# untitled.net
KiCad netlist of a schematic drawn in EAGLE
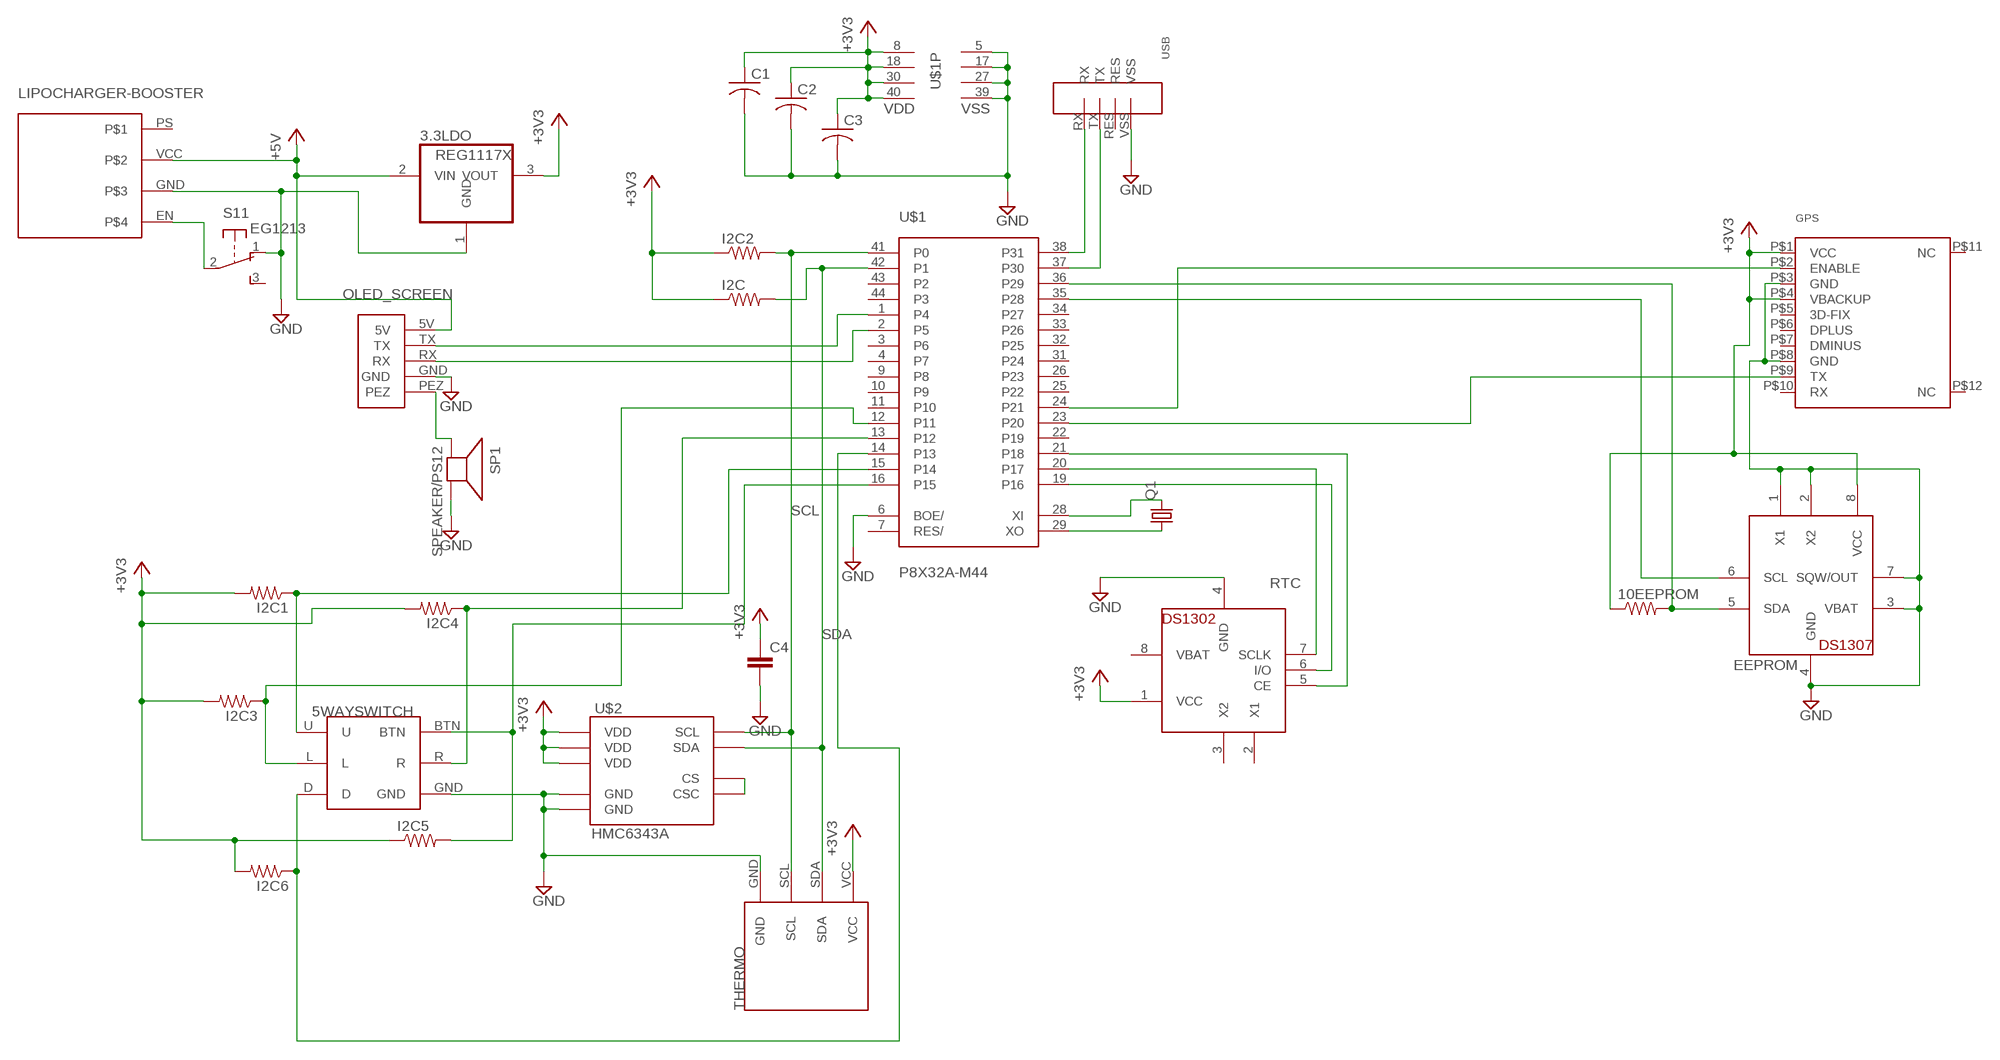
[diagram p0: schematic, sheet 1]

(export (version "E")
  (design (tool "Eeschema 10.0.6"))
  (components
    (comp (ref "3.3LDO")
      (value "REG1117X")
      (footprint "eagle-import:TO252")
      (libsource (lib "eagle-import") (part "REG1117X"))
    )
    (comp (ref "5WAYSWITCH")
      (value "5-WAYSWITCH")
      (footprint "eagle-import:5-WAYSWITCH")
      (libsource (lib "eagle-import") (part "5-WAYSWITCH"))
    )
    (comp (ref "10EEPROM")
      (value "R-US_R1005")
      (footprint "eagle-import:R1005")
      (libsource (lib "eagle-import") (part "R-US_R1005"))
    )
    (comp (ref "C1")
      (value "C-USC0603")
      (footprint "eagle-import:C0603")
      (libsource (lib "eagle-import") (part "C-USC0603"))
    )
    (comp (ref "C2")
      (value "C-USC0603")
      (footprint "eagle-import:C0603")
      (libsource (lib "eagle-import") (part "C-USC0603"))
    )
    (comp (ref "C3")
      (value "C-USC0603")
      (footprint "eagle-import:C0603")
      (libsource (lib "eagle-import") (part "C-USC0603"))
    )
    (comp (ref "C4")
      (value "CAP0603")
      (footprint "eagle-import:0603")
      (libsource (lib "eagle-import") (part "CAP0603"))
    )
    (comp (ref "EEPROM")
      (value "DS1307")
      (footprint "eagle-import:DIL08")
      (libsource (lib "eagle-import") (part "DS1307"))
    )
    (comp (ref "GPS")
      (value "GPS_FGPMMOPA6B")
      (footprint "eagle-import:FGPMMOPA6B")
      (libsource (lib "eagle-import") (part "GPS_FGPMMOPA6B"))
    )
    (comp (ref "I2C")
      (value "R-US_R1005")
      (footprint "eagle-import:R1005")
      (libsource (lib "eagle-import") (part "R-US_R1005"))
    )
    (comp (ref "I2C1")
      (value "R-US_R1005")
      (footprint "eagle-import:R1005")
      (libsource (lib "eagle-import") (part "R-US_R1005"))
    )
    (comp (ref "I2C2")
      (value "R-US_R1005")
      (footprint "eagle-import:R1005")
      (libsource (lib "eagle-import") (part "R-US_R1005"))
    )
    (comp (ref "I2C3")
      (value "R-US_R1005")
      (footprint "eagle-import:R1005")
      (libsource (lib "eagle-import") (part "R-US_R1005"))
    )
    (comp (ref "I2C4")
      (value "R-US_R1005")
      (footprint "eagle-import:R1005")
      (libsource (lib "eagle-import") (part "R-US_R1005"))
    )
    (comp (ref "I2C5")
      (value "R-US_R1005")
      (footprint "eagle-import:R1005")
      (libsource (lib "eagle-import") (part "R-US_R1005"))
    )
    (comp (ref "I2C6")
      (value "R-US_R1005")
      (footprint "eagle-import:R1005")
      (libsource (lib "eagle-import") (part "R-US_R1005"))
    )
    (comp (ref "LIPOCHARGER-BOOSTER")
      (value "SFLIPO")
      (footprint "eagle-import:SFLIPO")
      (libsource (lib "eagle-import") (part "SFLIPO"))
    )
    (comp (ref "OLED_SCREEN")
      (value "4DSCREEN")
      (footprint "eagle-import:4DSCREEN")
      (libsource (lib "eagle-import") (part "4DSCREEN"))
    )
    (comp (ref "Q1")
      (value "CRYSTALHC49S")
      (footprint "eagle-import:HC49_S")
      (libsource (lib "eagle-import") (part "CRYSTALHC49S"))
    )
    (comp (ref "RTC")
      (value "DS1302")
      (footprint "eagle-import:DIL08-ROUND")
      (libsource (lib "eagle-import") (part "DS1302"))
    )
    (comp (ref "S1")
      (value "EG1213")
      (footprint "eagle-import:EG1213")
      (libsource (lib "eagle-import") (part "EG1213"))
    )
    (comp (ref "SP1")
      (value "SPEAKER/PS12")
      (footprint "eagle-import:PS12")
      (libsource (lib "eagle-import") (part "SPEAKER/PS12"))
    )
    (comp (ref "THERMO")
      (value "SFTEMP")
      (footprint "eagle-import:SFTEMP")
      (libsource (lib "eagle-import") (part "SFTEMP"))
    )
    (comp (ref "U$1")
      (value "P8X32A-M44")
      (footprint "eagle-import:P8X32A-M44")
      (libsource (lib "eagle-import") (part "P8X32A-M44"))
    )
    (comp (ref "U$2")
      (value "HMC6343A")
      (footprint "eagle-import:LCC36")
      (libsource (lib "eagle-import") (part "HMC6343A"))
    )
    (comp (ref "USB")
      (value "4PINUSB")
      (footprint "eagle-import:4PINUSB")
      (libsource (lib "eagle-import") (part "4PINUSB"))
    )
  )
  (nets
    (net (code "1") (name "+3V3") (class "Default")
      (node (ref "10EEPROM") (pin "1") (pinfunction "1_1") (pintype "passive"))
      (node (ref "3.3LDO") (pin "3") (pinfunction "VOUT_3") (pintype "output"))
      (node (ref "C1") (pin "1") (pinfunction "1_1") (pintype "passive"))
      (node (ref "C2") (pin "1") (pinfunction "1_1") (pintype "passive"))
      (node (ref "C3") (pin "1") (pinfunction "1_1") (pintype "passive"))
      (node (ref "C4") (pin "1") (pinfunction "1_1") (pintype "passive"))
      (node (ref "EEPROM") (pin "8") (pinfunction "VCC_8") (pintype "power_in"))
      (node (ref "GPS") (pin "P$1") (pinfunction "VCC_P$1") (pintype "bidirectional"))
      (node (ref "GPS") (pin "P$4") (pinfunction "VBACKUP_P$4") (pintype "bidirectional"))
      (node (ref "I2C") (pin "1") (pinfunction "1_1") (pintype "passive"))
      (node (ref "I2C1") (pin "2") (pinfunction "2_2") (pintype "passive"))
      (node (ref "I2C2") (pin "1") (pinfunction "1_1") (pintype "passive"))
      (node (ref "I2C3") (pin "2") (pinfunction "2_2") (pintype "passive"))
      (node (ref "I2C4") (pin "2") (pinfunction "2_2") (pintype "passive"))
      (node (ref "I2C5") (pin "1") (pinfunction "1_1") (pintype "passive"))
      (node (ref "I2C6") (pin "2") (pinfunction "2_2") (pintype "passive"))
      (node (ref "RTC") (pin "1") (pinfunction "VCC_1") (pintype "power_in"))
      (node (ref "THERMO") (pin "VCC") (pinfunction "VCC_VCC") (pintype "bidirectional"))
      (node (ref "U$1") (pin "18") (pinfunction "VDD_18") (pintype "power_in"))
      (node (ref "U$1") (pin "30") (pinfunction "VDD_30") (pintype "power_in"))
      (node (ref "U$1") (pin "40") (pinfunction "VDD_40") (pintype "power_in"))
      (node (ref "U$1") (pin "8") (pinfunction "VDD_8") (pintype "power_in"))
      (node (ref "U$2") (pin "11") (pinfunction "VDD_11") (pintype "bidirectional"))
      (node (ref "U$2") (pin "21") (pinfunction "VDD_21") (pintype "bidirectional"))
      (node (ref "U$2") (pin "3") (pinfunction "VDD_3") (pintype "bidirectional"))
    )
    (net (code "2") (name "+5V") (class "Default")
      (node (ref "3.3LDO") (pin "2") (pinfunction "VIN_2") (pintype "input"))
      (node (ref "LIPOCHARGER-BOOSTER") (pin "VCC") (pinfunction "P$2_VCC") (pintype "bidirectional"))
      (node (ref "OLED_SCREEN") (pin "5V") (pinfunction "5V_5V") (pintype "bidirectional"))
    )
    (net (code "3") (name "/SCL") (class "Default")
      (node (ref "I2C2") (pin "2") (pinfunction "2_2") (pintype "passive"))
      (node (ref "THERMO") (pin "SCL") (pinfunction "SCL_SCL") (pintype "bidirectional"))
      (node (ref "U$1") (pin "41") (pinfunction "P0_41") (pintype "bidirectional"))
      (node (ref "U$2") (pin "32") (pinfunction "SCL_32") (pintype "bidirectional"))
    )
    (net (code "4") (name "/SDA") (class "Default")
      (node (ref "I2C") (pin "2") (pinfunction "2_2") (pintype "passive"))
      (node (ref "THERMO") (pin "SDA") (pinfunction "SDA_SDA") (pintype "bidirectional"))
      (node (ref "U$1") (pin "42") (pinfunction "P1_42") (pintype "bidirectional"))
      (node (ref "U$2") (pin "36") (pinfunction "SDA_36") (pintype "bidirectional"))
    )
    (net (code "5") (name "/VBAT") (class "Default")
      (node (ref "RTC") (pin "8") (pinfunction "VBAT_8") (pintype "power_in"))
    )
    (net (code "6") (name "GND") (class "Default")
      (node (ref "3.3LDO") (pin "1") (pinfunction "GND_1") (pintype "power_in"))
      (node (ref "5WAYSWITCH") (pin "GND") (pinfunction "GND_GND") (pintype "bidirectional"))
      (node (ref "C1") (pin "2") (pinfunction "2_2") (pintype "passive"))
      (node (ref "C2") (pin "2") (pinfunction "2_2") (pintype "passive"))
      (node (ref "C3") (pin "2") (pinfunction "2_2") (pintype "passive"))
      (node (ref "C4") (pin "2") (pinfunction "2_2") (pintype "passive"))
      (node (ref "EEPROM") (pin "1") (pinfunction "X1_1") (pintype "passive"))
      (node (ref "EEPROM") (pin "2") (pinfunction "X2_2") (pintype "passive"))
      (node (ref "EEPROM") (pin "3") (pinfunction "VBAT_3") (pintype "power_in"))
      (node (ref "EEPROM") (pin "4") (pinfunction "GND_4") (pintype "power_in"))
      (node (ref "EEPROM") (pin "7") (pinfunction "SQW/OUT_7") (pintype "bidirectional"))
      (node (ref "GPS") (pin "P$3") (pinfunction "GND_P$3") (pintype "bidirectional"))
      (node (ref "GPS") (pin "P$8") (pinfunction "GND_P$8") (pintype "bidirectional"))
      (node (ref "LIPOCHARGER-BOOSTER") (pin "GND") (pinfunction "P$3_GND") (pintype "bidirectional"))
      (node (ref "OLED_SCREEN") (pin "GND") (pinfunction "GND_GND") (pintype "bidirectional"))
      (node (ref "RTC") (pin "4") (pinfunction "GND_4") (pintype "power_in"))
      (node (ref "S1") (pin "1") (pinfunction "O_1") (pintype "passive"))
      (node (ref "SP1") (pin "P$2") (pinfunction "-_P$2") (pintype "passive"))
      (node (ref "THERMO") (pin "GND") (pinfunction "GND_GND") (pintype "bidirectional"))
      (node (ref "U$1") (pin "17") (pinfunction "VSS_17") (pintype "power_in"))
      (node (ref "U$1") (pin "27") (pinfunction "VSS_27") (pintype "power_in"))
      (node (ref "U$1") (pin "39") (pinfunction "VSS_39") (pintype "power_in"))
      (node (ref "U$1") (pin "5") (pinfunction "VSS_5") (pintype "power_in"))
      (node (ref "U$1") (pin "6") (pinfunction "BOE/_6") (pintype "input"))
      (node (ref "U$2") (pin "25") (pinfunction "GND_25") (pintype "bidirectional"))
      (node (ref "U$2") (pin "29") (pinfunction "GND_29") (pintype "bidirectional"))
      (node (ref "USB") (pin "VSS") (pinfunction "VSS_VSS") (pintype "bidirectional"))
    )
    (net (code "7") (name "Net-(EEPROM-SCL)") (class "Default")
      (node (ref "EEPROM") (pin "6") (pinfunction "SCL_6") (pintype "bidirectional"))
      (node (ref "U$1") (pin "35") (pinfunction "P28_35") (pintype "bidirectional"))
    )
    (net (code "8") (name "Net-(EEPROM-SDA)") (class "Default")
      (node (ref "10EEPROM") (pin "2") (pinfunction "2_2") (pintype "passive"))
      (node (ref "EEPROM") (pin "5") (pinfunction "SDA_5") (pintype "bidirectional"))
      (node (ref "U$1") (pin "36") (pinfunction "P29_36") (pintype "bidirectional"))
    )
    (net (code "9") (name "Net-(GPS-ENABLE)") (class "Default")
      (node (ref "GPS") (pin "P$2") (pinfunction "ENABLE_P$2") (pintype "bidirectional"))
      (node (ref "U$1") (pin "24") (pinfunction "P21_24") (pintype "bidirectional"))
    )
    (net (code "10") (name "Net-(GPS-TX)") (class "Default")
      (node (ref "GPS") (pin "P$9") (pinfunction "TX_P$9") (pintype "bidirectional"))
      (node (ref "U$1") (pin "23") (pinfunction "P20_23") (pintype "bidirectional"))
    )
    (net (code "11") (name "Net-(LIPOCHARGER-BOOSTER-P$4)") (class "Default")
      (node (ref "LIPOCHARGER-BOOSTER") (pin "EN") (pinfunction "P$4_EN") (pintype "bidirectional"))
      (node (ref "S1") (pin "2") (pinfunction "P_2") (pintype "passive"))
    )
    (net (code "12") (name "Net-(RTC-CE)") (class "Default")
      (node (ref "RTC") (pin "5") (pinfunction "CE_5") (pintype "input"))
      (node (ref "U$1") (pin "21") (pinfunction "P18_21") (pintype "bidirectional"))
    )
    (net (code "13") (name "Net-(RTC-I{slash}O)") (class "Default")
      (node (ref "RTC") (pin "6") (pinfunction "I/O_6") (pintype "bidirectional"))
      (node (ref "U$1") (pin "19") (pinfunction "P16_19") (pintype "bidirectional"))
    )
    (net (code "14") (name "Net-(RTC-SCLK)") (class "Default")
      (node (ref "RTC") (pin "7") (pinfunction "SCLK_7") (pintype "input"))
      (node (ref "U$1") (pin "20") (pinfunction "P17_20") (pintype "bidirectional"))
    )
    (net (code "15") (name "Net-(SP1-+)") (class "Default")
      (node (ref "OLED_SCREEN") (pin "PEZ") (pinfunction "PEZ_PEZ") (pintype "bidirectional"))
      (node (ref "SP1") (pin "P$1") (pinfunction "+_P$1") (pintype "passive"))
    )
    (net (code "16") (name "Net-(U$1A-P4)") (class "Default")
      (node (ref "OLED_SCREEN") (pin "TX") (pinfunction "TX_TX") (pintype "bidirectional"))
      (node (ref "U$1") (pin "1") (pinfunction "P4_1") (pintype "bidirectional"))
    )
    (net (code "17") (name "Net-(U$1A-P5)") (class "Default")
      (node (ref "OLED_SCREEN") (pin "RX") (pinfunction "RX_RX") (pintype "bidirectional"))
      (node (ref "U$1") (pin "2") (pinfunction "P5_2") (pintype "bidirectional"))
    )
    (net (code "18") (name "Net-(U$1A-P11)") (class "Default")
      (node (ref "5WAYSWITCH") (pin "L") (pinfunction "L_L") (pintype "bidirectional"))
      (node (ref "I2C3") (pin "1") (pinfunction "1_1") (pintype "passive"))
      (node (ref "U$1") (pin "12") (pinfunction "P11_12") (pintype "bidirectional"))
    )
    (net (code "19") (name "Net-(U$1A-P12)") (class "Default")
      (node (ref "5WAYSWITCH") (pin "R") (pinfunction "R_R") (pintype "bidirectional"))
      (node (ref "I2C4") (pin "1") (pinfunction "1_1") (pintype "passive"))
      (node (ref "U$1") (pin "13") (pinfunction "P12_13") (pintype "bidirectional"))
    )
    (net (code "20") (name "Net-(U$1A-P13)") (class "Default")
      (node (ref "5WAYSWITCH") (pin "D") (pinfunction "D_D") (pintype "bidirectional"))
      (node (ref "I2C6") (pin "1") (pinfunction "1_1") (pintype "passive"))
      (node (ref "U$1") (pin "14") (pinfunction "P13_14") (pintype "bidirectional"))
    )
    (net (code "21") (name "Net-(U$1A-P14)") (class "Default")
      (node (ref "5WAYSWITCH") (pin "U") (pinfunction "U_U") (pintype "bidirectional"))
      (node (ref "I2C1") (pin "1") (pinfunction "1_1") (pintype "passive"))
      (node (ref "U$1") (pin "15") (pinfunction "P14_15") (pintype "bidirectional"))
    )
    (net (code "22") (name "Net-(U$1A-P15)") (class "Default")
      (node (ref "5WAYSWITCH") (pin "BTN") (pinfunction "BTN_BTN") (pintype "bidirectional"))
      (node (ref "I2C5") (pin "2") (pinfunction "2_2") (pintype "passive"))
      (node (ref "U$1") (pin "16") (pinfunction "P15_16") (pintype "bidirectional"))
    )
    (net (code "23") (name "Net-(U$1A-P30)") (class "Default")
      (node (ref "U$1") (pin "37") (pinfunction "P30_37") (pintype "bidirectional"))
      (node (ref "USB") (pin "TX") (pinfunction "TX_TX") (pintype "bidirectional"))
    )
    (net (code "24") (name "Net-(U$1A-P31)") (class "Default")
      (node (ref "U$1") (pin "38") (pinfunction "P31_38") (pintype "bidirectional"))
      (node (ref "USB") (pin "RX") (pinfunction "RX_RX") (pintype "bidirectional"))
    )
    (net (code "25") (name "Net-(U$1A-XI)") (class "Default")
      (node (ref "Q1") (pin "2") (pinfunction "2_2") (pintype "passive"))
      (node (ref "U$1") (pin "28") (pinfunction "XI_28") (pintype "input"))
    )
    (net (code "26") (name "Net-(U$1A-XO)") (class "Default")
      (node (ref "Q1") (pin "1") (pinfunction "1_1") (pintype "passive"))
      (node (ref "U$1") (pin "29") (pinfunction "XO_29") (pintype "output"))
    )
    (net (code "27") (name "Net-(U$2-CS)") (class "Default")
      (node (ref "U$2") (pin "22") (pinfunction "CS_22") (pintype "bidirectional"))
      (node (ref "U$2") (pin "35") (pinfunction "CSC_35") (pintype "bidirectional"))
    )
    (net (code "28") (name "unconnected-(GPS-3D-FIX-PadP$5)") (class "Default")
      (node (ref "GPS") (pin "P$5") (pinfunction "3D-FIX_P$5") (pintype "bidirectional"))
    )
    (net (code "29") (name "unconnected-(GPS-DMINUS-PadP$7)") (class "Default")
      (node (ref "GPS") (pin "P$7") (pinfunction "DMINUS_P$7") (pintype "bidirectional"))
    )
    (net (code "30") (name "unconnected-(GPS-DPLUS-PadP$6)") (class "Default")
      (node (ref "GPS") (pin "P$6") (pinfunction "DPLUS_P$6") (pintype "bidirectional"))
    )
    (net (code "31") (name "unconnected-(GPS-NC-PadP$11)") (class "Default")
      (node (ref "GPS") (pin "P$11") (pinfunction "NC_P$11") (pintype "bidirectional"))
    )
    (net (code "32") (name "unconnected-(GPS-NC-PadP$12)") (class "Default")
      (node (ref "GPS") (pin "P$12") (pinfunction "NC_P$12") (pintype "bidirectional"))
    )
    (net (code "33") (name "unconnected-(GPS-RX-PadP$10)") (class "Default")
      (node (ref "GPS") (pin "P$10") (pinfunction "RX_P$10") (pintype "bidirectional"))
    )
    (net (code "34") (name "unconnected-(LIPOCHARGER-BOOSTER-P$1-PadPS)") (class "Default")
      (node (ref "LIPOCHARGER-BOOSTER") (pin "PS") (pinfunction "P$1_PS") (pintype "bidirectional"))
    )
    (net (code "35") (name "unconnected-(RTC-X1-Pad2)") (class "Default")
      (node (ref "RTC") (pin "2") (pinfunction "X1_2") (pintype "passive"))
    )
    (net (code "36") (name "unconnected-(RTC-X2-Pad3)") (class "Default")
      (node (ref "RTC") (pin "3") (pinfunction "X2_3") (pintype "passive"))
    )
    (net (code "37") (name "unconnected-(S1A-S-Pad3)") (class "Default")
      (node (ref "S1") (pin "3") (pinfunction "S_3") (pintype "passive"))
    )
    (net (code "38") (name "unconnected-(U$1A-P2-Pad43)") (class "Default")
      (node (ref "U$1") (pin "43") (pinfunction "P2_43") (pintype "bidirectional"))
    )
    (net (code "39") (name "unconnected-(U$1A-P3-Pad44)") (class "Default")
      (node (ref "U$1") (pin "44") (pinfunction "P3_44") (pintype "bidirectional"))
    )
    (net (code "40") (name "unconnected-(U$1A-P6-Pad3)") (class "Default")
      (node (ref "U$1") (pin "3") (pinfunction "P6_3") (pintype "bidirectional"))
    )
    (net (code "41") (name "unconnected-(U$1A-P7-Pad4)") (class "Default")
      (node (ref "U$1") (pin "4") (pinfunction "P7_4") (pintype "bidirectional"))
    )
    (net (code "42") (name "unconnected-(U$1A-P8-Pad9)") (class "Default")
      (node (ref "U$1") (pin "9") (pinfunction "P8_9") (pintype "bidirectional"))
    )
    (net (code "43") (name "unconnected-(U$1A-P9-Pad10)") (class "Default")
      (node (ref "U$1") (pin "10") (pinfunction "P9_10") (pintype "bidirectional"))
    )
    (net (code "44") (name "unconnected-(U$1A-P10-Pad11)") (class "Default")
      (node (ref "U$1") (pin "11") (pinfunction "P10_11") (pintype "bidirectional"))
    )
    (net (code "45") (name "unconnected-(U$1A-P19-Pad22)") (class "Default")
      (node (ref "U$1") (pin "22") (pinfunction "P19_22") (pintype "bidirectional"))
    )
    (net (code "46") (name "unconnected-(U$1A-P22-Pad25)") (class "Default")
      (node (ref "U$1") (pin "25") (pinfunction "P22_25") (pintype "bidirectional"))
    )
    (net (code "47") (name "unconnected-(U$1A-P23-Pad26)") (class "Default")
      (node (ref "U$1") (pin "26") (pinfunction "P23_26") (pintype "bidirectional"))
    )
    (net (code "48") (name "unconnected-(U$1A-P24-Pad31)") (class "Default")
      (node (ref "U$1") (pin "31") (pinfunction "P24_31") (pintype "bidirectional"))
    )
    (net (code "49") (name "unconnected-(U$1A-P25-Pad32)") (class "Default")
      (node (ref "U$1") (pin "32") (pinfunction "P25_32") (pintype "bidirectional"))
    )
    (net (code "50") (name "unconnected-(U$1A-P26-Pad33)") (class "Default")
      (node (ref "U$1") (pin "33") (pinfunction "P26_33") (pintype "bidirectional"))
    )
    (net (code "51") (name "unconnected-(U$1A-P27-Pad34)") (class "Default")
      (node (ref "U$1") (pin "34") (pinfunction "P27_34") (pintype "bidirectional"))
    )
    (net (code "52") (name "unconnected-(U$1A-RES{slash}-Pad7)") (class "Default")
      (node (ref "U$1") (pin "7") (pinfunction "RES/_7") (pintype "bidirectional"))
    )
    (net (code "53") (name "unconnected-(USB-PadRES)") (class "Default")
      (node (ref "USB") (pin "RES") (pinfunction "RES_RES") (pintype "bidirectional"))
    )
  )
)
